# Top_Level.net
KiCad netlist of a schematic drawn in Altium Designer
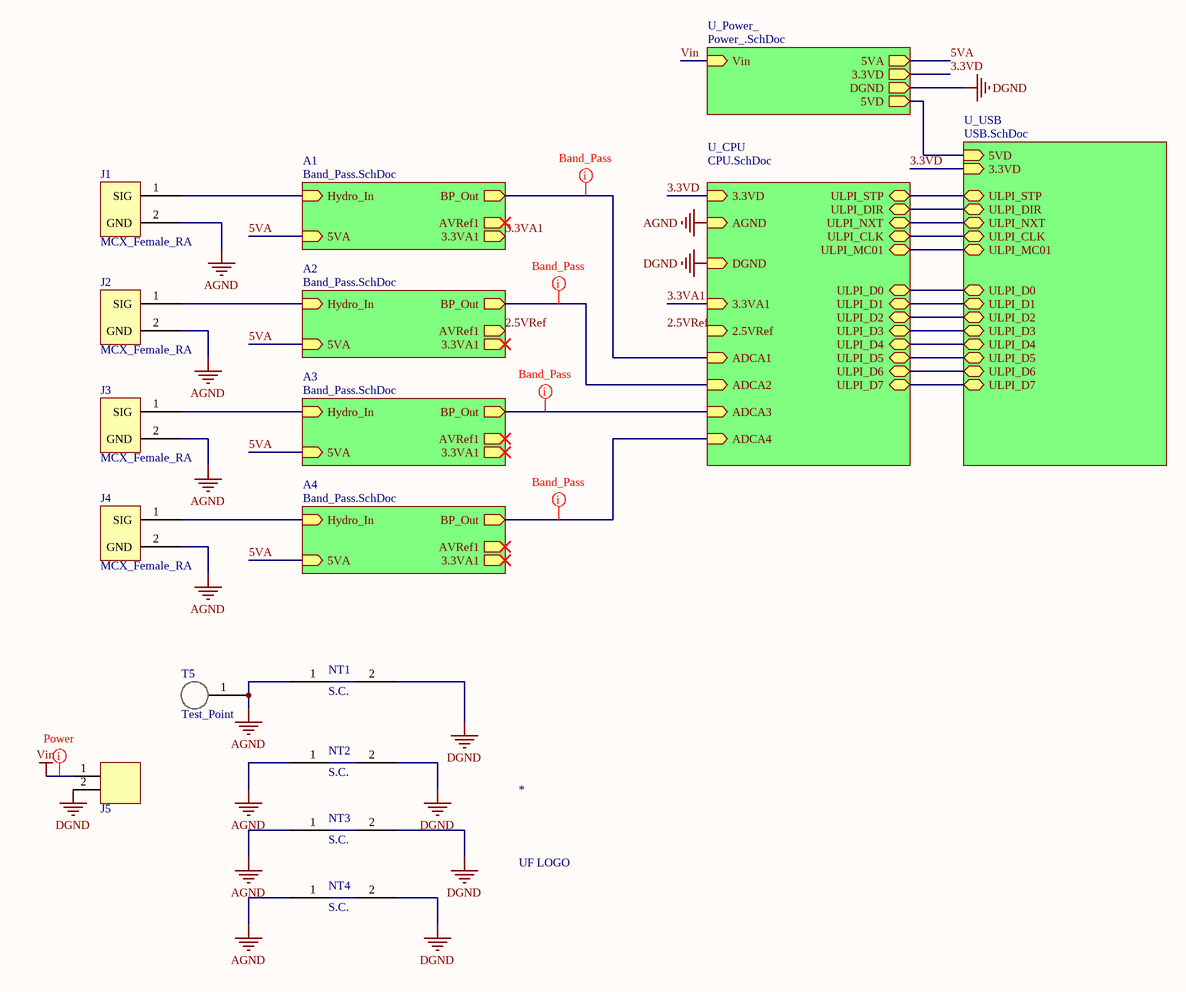
[diagram p0: Top_Level.SchDoc]

(export (version "E")
  (design (tool "Eeschema 10.0.6"))
  (components
    (comp (ref "*")
      (value "UF LOGO")
      (footprint "UF LOGO-1000")
      (libsource (lib "Hydrophone") (part "UF LOGO"))
    )
    (comp (ref "J1")
      (value "MCX_Female_RA")
      (footprint "MCX_Female")
      (description "CONN MCX JACK R/A 50 OHM PCB")
      (libsource (lib "Hydrophone") (part "MCX_Female_RA"))
    )
    (comp (ref "J2")
      (value "MCX_Female_RA")
      (footprint "MCX_Female")
      (description "CONN MCX JACK R/A 50 OHM PCB")
      (libsource (lib "Hydrophone") (part "MCX_Female_RA"))
    )
    (comp (ref "J3")
      (value "MCX_Female_RA")
      (footprint "MCX_Female")
      (description "CONN MCX JACK R/A 50 OHM PCB")
      (libsource (lib "Hydrophone") (part "MCX_Female_RA"))
    )
    (comp (ref "J4")
      (value "MCX_Female_RA")
      (footprint "MCX_Female")
      (description "CONN MCX JACK R/A 50 OHM PCB")
      (libsource (lib "Hydrophone") (part "MCX_Female_RA"))
    )
    (comp (ref "J5")
      (value "2-pin Horz Sherlock")
      (footprint "MOLEX-HDR-1X2-SHERLOCK-HORZ")
      (fields
        (field (name "MANUFACTURER PART NUMBER") "0353630260")
        (field (name "MANUFACTURER") "Molex Inc")
      )
      (libsource (lib "Connectors") (part "MOLEX-HDR-1x2-SHERLOCK_RA"))
    )
    (comp (ref "MIL")
      (value "MIL LOGO")
      (footprint "MIL LOGO - 500")
      (libsource (lib "Hydrophone") (part "MIL LOGO"))
    )
    (comp (ref "NT1") (value "S.C.") (footprint "Net_Tie") (libsource (lib "Hydrophone") (part "Net_Tie")))
    (comp (ref "NT2") (value "S.C.") (footprint "Net_Tie") (libsource (lib "Hydrophone") (part "Net_Tie")))
    (comp (ref "NT3") (value "S.C.") (footprint "Net_Tie") (libsource (lib "Hydrophone") (part "Net_Tie")))
    (comp (ref "NT4") (value "S.C.") (footprint "Net_Tie") (libsource (lib "Hydrophone") (part "Net_Tie")))
    (comp (ref "T5")
      (value "Test_Point")
      (footprint "TP")
      (description "TEST POINT PC COMPACT .063\"D")
      (libsource (lib "Hydrophone") (part "Test_Point"))
    )
  )
  (nets
    (net (code "17") (name "/Hydro_In") (class "Default")
      (node (ref "J4") (pin "1") (pinfunction "SIG_1") (pintype "passive"))
    )
    (net (code "18") (name "/Hydro_In_1") (class "Default")
      (node (ref "J1") (pin "1") (pinfunction "SIG_1") (pintype "passive"))
    )
    (net (code "19") (name "/Hydro_In_2") (class "Default")
      (node (ref "J2") (pin "1") (pinfunction "SIG_1") (pintype "passive"))
    )
    (net (code "20") (name "/Hydro_In_3") (class "Default")
      (node (ref "J3") (pin "1") (pinfunction "SIG_1") (pintype "passive"))
    )
    (net (code "34") (name "AGND") (class "Default")
      (node (ref "J1") (pin "2") (pinfunction "GND_2") (pintype "passive"))
      (node (ref "J2") (pin "2") (pinfunction "GND_2") (pintype "passive"))
      (node (ref "J3") (pin "2") (pinfunction "GND_2") (pintype "passive"))
      (node (ref "J4") (pin "2") (pinfunction "GND_2") (pintype "passive"))
      (node (ref "NT1") (pin "1") (pintype "passive"))
      (node (ref "NT2") (pin "1") (pintype "passive"))
      (node (ref "NT3") (pin "1") (pintype "passive"))
      (node (ref "NT4") (pin "1") (pintype "passive"))
      (node (ref "T5") (pin "1") (pintype "passive"))
    )
    (net (code "35") (name "DGND") (class "Default")
      (node (ref "J5") (pin "2") (pinfunction "2_2") (pintype "passive"))
      (node (ref "NT1") (pin "2") (pintype "passive"))
      (node (ref "NT2") (pin "2") (pintype "passive"))
      (node (ref "NT3") (pin "2") (pintype "passive"))
      (node (ref "NT4") (pin "2") (pintype "passive"))
    )
    (net (code "36") (name "Vin") (class "Default")
      (node (ref "J5") (pin "1") (pinfunction "1_1") (pintype "passive"))
    )
  )
)
